# 04_DUT_Connector.net
KiCad netlist of a schematic drawn in Altium Designer
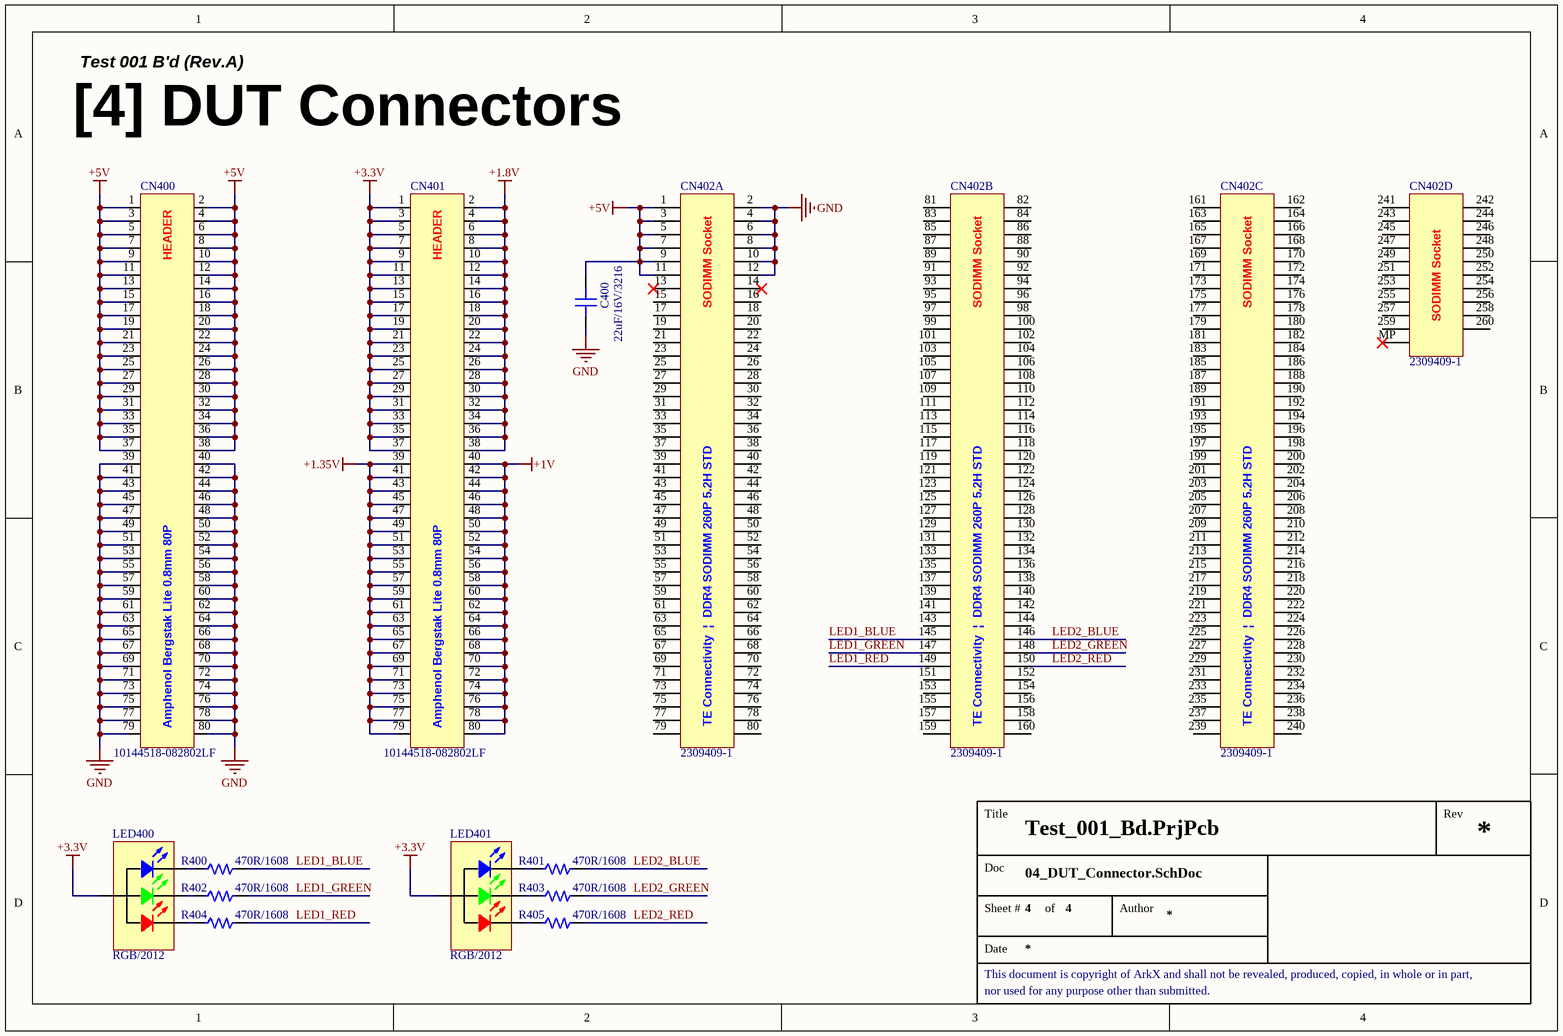
[diagram p0: 04_DUT_Connector.SchDoc]

(export (version "E")
  (design (tool "Eeschema 10.0.6"))
  (components
    (comp (ref "C400")
      (value "22uF/16V/3216")
      (footprint "CAP 3216 (1206_INCH) - H1.8MM")
      (description "Ceramic CAP_22uF/16V/3216")
      (fields (field (name "LCSC PART #") "C12891"))
      (libsource (lib "Arkx") (part "CAP_22uF/16V/3216"))
    )
    (comp (ref "CN400")
      (value "10144518-082802LF")
      (footprint "10144518-082802LF")
      (description "BergStak® Lite 0.80mm, Board-to-Board Connector, 80 Positions, Dual Row, Vertical Header")
      (fields (field (name "MANUFACTURER") "Amphenol"))
      (libsource (lib "Arkx") (part "CON_10144518-082802LF"))
    )
    (comp (ref "CN401")
      (value "10144518-082802LF")
      (footprint "10144518-082802LF")
      (description "BergStak® Lite 0.80mm, Board-to-Board Connector, 80 Positions, Dual Row, Vertical Header")
      (fields (field (name "MANUFACTURER") "Amphenol"))
      (libsource (lib "Arkx") (part "CON_10144518-082802LF"))
    )
    (comp (ref "CN402")
      (value "2309409-1")
      (footprint "CON_SODIMM_2309409-1")
      (fields (field (name "MANUFACTURER") "TE Connectivity") (field (name "LCSC PART #") "C5164025"))
      (libsource (lib "Arkx") (part "CON_SODIMM_2309409-1"))
    )
    (comp (ref "LED400")
      (value "RGB/2012")
      (footprint "LED MHT170RGBCT")
      (fields (field (name "LCSC PART #") "C2962094"))
      (libsource (lib "Arkx") (part "LED_RGB_MHT170RGBCT"))
    )
    (comp (ref "LED401")
      (value "RGB/2012")
      (footprint "LED MHT170RGBCT")
      (fields (field (name "LCSC PART #") "C2962094"))
      (libsource (lib "Arkx") (part "LED_RGB_MHT170RGBCT"))
    )
    (comp (ref "R400")
      (value "470R/1608")
      (footprint "RES 1608 (0603_inch)")
      (description "RES_470R/1608/0.1W")
      (fields (field (name "LCSC PART #") "C23179"))
      (libsource (lib "Arkx") (part "RES_470R/1608/0.1W"))
    )
    (comp (ref "R401")
      (value "470R/1608")
      (footprint "RES 1608 (0603_inch)")
      (description "RES_470R/1608/0.1W")
      (fields (field (name "LCSC PART #") "C23179"))
      (libsource (lib "Arkx") (part "RES_470R/1608/0.1W"))
    )
    (comp (ref "R402")
      (value "470R/1608")
      (footprint "RES 1608 (0603_inch)")
      (description "RES_470R/1608/0.1W")
      (fields (field (name "LCSC PART #") "C23179"))
      (libsource (lib "Arkx") (part "RES_470R/1608/0.1W"))
    )
    (comp (ref "R403")
      (value "470R/1608")
      (footprint "RES 1608 (0603_inch)")
      (description "RES_470R/1608/0.1W")
      (fields (field (name "LCSC PART #") "C23179"))
      (libsource (lib "Arkx") (part "RES_470R/1608/0.1W"))
    )
    (comp (ref "R404")
      (value "470R/1608")
      (footprint "RES 1608 (0603_inch)")
      (description "RES_470R/1608/0.1W")
      (fields (field (name "LCSC PART #") "C23179"))
      (libsource (lib "Arkx") (part "RES_470R/1608/0.1W"))
    )
    (comp (ref "R405")
      (value "470R/1608")
      (footprint "RES 1608 (0603_inch)")
      (description "RES_470R/1608/0.1W")
      (fields (field (name "LCSC PART #") "C23179"))
      (libsource (lib "Arkx") (part "RES_470R/1608/0.1W"))
    )
  )
  (nets
    (net (code "1") (name "+1.8V") (class "Default")
      (node (ref "CN401") (pin "10") (pintype "passive"))
      (node (ref "CN401") (pin "12") (pintype "passive"))
      (node (ref "CN401") (pin "14") (pintype "passive"))
      (node (ref "CN401") (pin "16") (pintype "passive"))
      (node (ref "CN401") (pin "18") (pintype "passive"))
      (node (ref "CN401") (pin "2") (pintype "passive"))
      (node (ref "CN401") (pin "20") (pintype "passive"))
      (node (ref "CN401") (pin "22") (pintype "passive"))
      (node (ref "CN401") (pin "24") (pintype "passive"))
      (node (ref "CN401") (pin "26") (pintype "passive"))
      (node (ref "CN401") (pin "28") (pintype "passive"))
      (node (ref "CN401") (pin "30") (pintype "passive"))
      (node (ref "CN401") (pin "32") (pintype "passive"))
      (node (ref "CN401") (pin "34") (pintype "passive"))
      (node (ref "CN401") (pin "36") (pintype "passive"))
      (node (ref "CN401") (pin "38") (pintype "passive"))
      (node (ref "CN401") (pin "4") (pintype "passive"))
      (node (ref "CN401") (pin "6") (pintype "passive"))
      (node (ref "CN401") (pin "8") (pintype "passive"))
    )
    (net (code "2") (name "+1.35V") (class "Default")
      (node (ref "CN401") (pin "39") (pintype "passive"))
      (node (ref "CN401") (pin "41") (pintype "passive"))
      (node (ref "CN401") (pin "43") (pintype "passive"))
      (node (ref "CN401") (pin "45") (pintype "passive"))
      (node (ref "CN401") (pin "47") (pintype "passive"))
      (node (ref "CN401") (pin "49") (pintype "passive"))
      (node (ref "CN401") (pin "51") (pintype "passive"))
      (node (ref "CN401") (pin "53") (pintype "passive"))
      (node (ref "CN401") (pin "55") (pintype "passive"))
      (node (ref "CN401") (pin "57") (pintype "passive"))
      (node (ref "CN401") (pin "59") (pintype "passive"))
      (node (ref "CN401") (pin "61") (pintype "passive"))
      (node (ref "CN401") (pin "63") (pintype "passive"))
      (node (ref "CN401") (pin "65") (pintype "passive"))
      (node (ref "CN401") (pin "67") (pintype "passive"))
      (node (ref "CN401") (pin "69") (pintype "passive"))
      (node (ref "CN401") (pin "71") (pintype "passive"))
      (node (ref "CN401") (pin "73") (pintype "passive"))
      (node (ref "CN401") (pin "75") (pintype "passive"))
      (node (ref "CN401") (pin "77") (pintype "passive"))
      (node (ref "CN401") (pin "79") (pintype "passive"))
    )
    (net (code "3") (name "+1V") (class "Default")
      (node (ref "CN401") (pin "40") (pintype "passive"))
      (node (ref "CN401") (pin "42") (pintype "passive"))
      (node (ref "CN401") (pin "44") (pintype "passive"))
      (node (ref "CN401") (pin "46") (pintype "passive"))
      (node (ref "CN401") (pin "48") (pintype "passive"))
      (node (ref "CN401") (pin "50") (pintype "passive"))
      (node (ref "CN401") (pin "52") (pintype "passive"))
      (node (ref "CN401") (pin "54") (pintype "passive"))
      (node (ref "CN401") (pin "56") (pintype "passive"))
      (node (ref "CN401") (pin "58") (pintype "passive"))
      (node (ref "CN401") (pin "60") (pintype "passive"))
      (node (ref "CN401") (pin "62") (pintype "passive"))
      (node (ref "CN401") (pin "64") (pintype "passive"))
      (node (ref "CN401") (pin "66") (pintype "passive"))
      (node (ref "CN401") (pin "68") (pintype "passive"))
      (node (ref "CN401") (pin "70") (pintype "passive"))
      (node (ref "CN401") (pin "72") (pintype "passive"))
      (node (ref "CN401") (pin "74") (pintype "passive"))
      (node (ref "CN401") (pin "76") (pintype "passive"))
      (node (ref "CN401") (pin "78") (pintype "passive"))
      (node (ref "CN401") (pin "80") (pintype "passive"))
    )
    (net (code "4") (name "+3.3V") (class "Default")
      (node (ref "CN401") (pin "1") (pintype "passive"))
      (node (ref "CN401") (pin "11") (pintype "passive"))
      (node (ref "CN401") (pin "13") (pintype "passive"))
      (node (ref "CN401") (pin "15") (pintype "passive"))
      (node (ref "CN401") (pin "17") (pintype "passive"))
      (node (ref "CN401") (pin "19") (pintype "passive"))
      (node (ref "CN401") (pin "21") (pintype "passive"))
      (node (ref "CN401") (pin "23") (pintype "passive"))
      (node (ref "CN401") (pin "25") (pintype "passive"))
      (node (ref "CN401") (pin "27") (pintype "passive"))
      (node (ref "CN401") (pin "29") (pintype "passive"))
      (node (ref "CN401") (pin "3") (pintype "passive"))
      (node (ref "CN401") (pin "31") (pintype "passive"))
      (node (ref "CN401") (pin "33") (pintype "passive"))
      (node (ref "CN401") (pin "35") (pintype "passive"))
      (node (ref "CN401") (pin "37") (pintype "passive"))
      (node (ref "CN401") (pin "5") (pintype "passive"))
      (node (ref "CN401") (pin "7") (pintype "passive"))
      (node (ref "CN401") (pin "9") (pintype "passive"))
      (node (ref "LED400") (pin "4") (pinfunction "Common_Anode_4") (pintype "passive"))
      (node (ref "LED401") (pin "4") (pinfunction "Common_Anode_4") (pintype "passive"))
    )
    (net (code "5") (name "+5V") (class "Default")
      (node (ref "C400") (pin "2") (pinfunction "2_2") (pintype "passive"))
      (node (ref "CN400") (pin "1") (pintype "passive"))
      (node (ref "CN400") (pin "10") (pintype "passive"))
      (node (ref "CN400") (pin "11") (pintype "passive"))
      (node (ref "CN400") (pin "12") (pintype "passive"))
      (node (ref "CN400") (pin "13") (pintype "passive"))
      (node (ref "CN400") (pin "14") (pintype "passive"))
      (node (ref "CN400") (pin "15") (pintype "passive"))
      (node (ref "CN400") (pin "16") (pintype "passive"))
      (node (ref "CN400") (pin "17") (pintype "passive"))
      (node (ref "CN400") (pin "18") (pintype "passive"))
      (node (ref "CN400") (pin "19") (pintype "passive"))
      (node (ref "CN400") (pin "2") (pintype "passive"))
      (node (ref "CN400") (pin "20") (pintype "passive"))
      (node (ref "CN400") (pin "21") (pintype "passive"))
      (node (ref "CN400") (pin "22") (pintype "passive"))
      (node (ref "CN400") (pin "23") (pintype "passive"))
      (node (ref "CN400") (pin "24") (pintype "passive"))
      (node (ref "CN400") (pin "25") (pintype "passive"))
      (node (ref "CN400") (pin "26") (pintype "passive"))
      (node (ref "CN400") (pin "27") (pintype "passive"))
      (node (ref "CN400") (pin "28") (pintype "passive"))
      (node (ref "CN400") (pin "29") (pintype "passive"))
      (node (ref "CN400") (pin "3") (pintype "passive"))
      (node (ref "CN400") (pin "30") (pintype "passive"))
      (node (ref "CN400") (pin "31") (pintype "passive"))
      (node (ref "CN400") (pin "32") (pintype "passive"))
      (node (ref "CN400") (pin "33") (pintype "passive"))
      (node (ref "CN400") (pin "34") (pintype "passive"))
      (node (ref "CN400") (pin "35") (pintype "passive"))
      (node (ref "CN400") (pin "36") (pintype "passive"))
      (node (ref "CN400") (pin "37") (pintype "passive"))
      (node (ref "CN400") (pin "38") (pintype "passive"))
      (node (ref "CN400") (pin "4") (pintype "passive"))
      (node (ref "CN400") (pin "5") (pintype "passive"))
      (node (ref "CN400") (pin "6") (pintype "passive"))
      (node (ref "CN400") (pin "7") (pintype "passive"))
      (node (ref "CN400") (pin "8") (pintype "passive"))
      (node (ref "CN400") (pin "9") (pintype "passive"))
      (node (ref "CN402") (pin "1") (pinfunction "1_1") (pintype "passive"))
      (node (ref "CN402") (pin "11") (pinfunction "11_11") (pintype "passive"))
      (node (ref "CN402") (pin "3") (pinfunction "3_3") (pintype "passive"))
      (node (ref "CN402") (pin "5") (pinfunction "5_5") (pintype "passive"))
      (node (ref "CN402") (pin "7") (pinfunction "7_7") (pintype "passive"))
      (node (ref "CN402") (pin "9") (pinfunction "9_9") (pintype "passive"))
    )
    (net (code "6") (name "/LED1_BLUE") (class "Default")
      (node (ref "CN402") (pin "145") (pinfunction "145_145") (pintype "passive"))
      (node (ref "R400") (pin "2") (pinfunction "2_2") (pintype "passive"))
    )
    (net (code "7") (name "/LED1_GREEN") (class "Default")
      (node (ref "CN402") (pin "147") (pinfunction "147_147") (pintype "passive"))
      (node (ref "R402") (pin "2") (pinfunction "2_2") (pintype "passive"))
    )
    (net (code "8") (name "/LED1_RED") (class "Default")
      (node (ref "CN402") (pin "149") (pinfunction "149_149") (pintype "passive"))
      (node (ref "R404") (pin "2") (pinfunction "2_2") (pintype "passive"))
    )
    (net (code "9") (name "/LED2_BLUE") (class "Default")
      (node (ref "CN402") (pin "146") (pinfunction "146_146") (pintype "passive"))
      (node (ref "R401") (pin "2") (pinfunction "2_2") (pintype "passive"))
    )
    (net (code "10") (name "/LED2_GREEN") (class "Default")
      (node (ref "CN402") (pin "148") (pinfunction "148_148") (pintype "passive"))
      (node (ref "R403") (pin "2") (pinfunction "2_2") (pintype "passive"))
    )
    (net (code "11") (name "/LED2_RED") (class "Default")
      (node (ref "CN402") (pin "150") (pinfunction "150_150") (pintype "passive"))
      (node (ref "R405") (pin "2") (pinfunction "2_2") (pintype "passive"))
    )
    (net (code "12") (name "GND") (class "Default")
      (node (ref "C400") (pin "1") (pinfunction "1_1") (pintype "passive"))
      (node (ref "CN400") (pin "39") (pintype "passive"))
      (node (ref "CN400") (pin "40") (pintype "passive"))
      (node (ref "CN400") (pin "41") (pintype "passive"))
      (node (ref "CN400") (pin "42") (pintype "passive"))
      (node (ref "CN400") (pin "43") (pintype "passive"))
      (node (ref "CN400") (pin "44") (pintype "passive"))
      (node (ref "CN400") (pin "45") (pintype "passive"))
      (node (ref "CN400") (pin "46") (pintype "passive"))
      (node (ref "CN400") (pin "47") (pintype "passive"))
      (node (ref "CN400") (pin "48") (pintype "passive"))
      (node (ref "CN400") (pin "49") (pintype "passive"))
      (node (ref "CN400") (pin "50") (pintype "passive"))
      (node (ref "CN400") (pin "51") (pintype "passive"))
      (node (ref "CN400") (pin "52") (pintype "passive"))
      (node (ref "CN400") (pin "53") (pintype "passive"))
      (node (ref "CN400") (pin "54") (pintype "passive"))
      (node (ref "CN400") (pin "55") (pintype "passive"))
      (node (ref "CN400") (pin "56") (pintype "passive"))
      (node (ref "CN400") (pin "57") (pintype "passive"))
      (node (ref "CN400") (pin "58") (pintype "passive"))
      (node (ref "CN400") (pin "59") (pintype "passive"))
      (node (ref "CN400") (pin "60") (pintype "passive"))
      (node (ref "CN400") (pin "61") (pintype "passive"))
      (node (ref "CN400") (pin "62") (pintype "passive"))
      (node (ref "CN400") (pin "63") (pintype "passive"))
      (node (ref "CN400") (pin "64") (pintype "passive"))
      (node (ref "CN400") (pin "65") (pintype "passive"))
      (node (ref "CN400") (pin "66") (pintype "passive"))
      (node (ref "CN400") (pin "67") (pintype "passive"))
      (node (ref "CN400") (pin "68") (pintype "passive"))
      (node (ref "CN400") (pin "69") (pintype "passive"))
      (node (ref "CN400") (pin "70") (pintype "passive"))
      (node (ref "CN400") (pin "71") (pintype "passive"))
      (node (ref "CN400") (pin "72") (pintype "passive"))
      (node (ref "CN400") (pin "73") (pintype "passive"))
      (node (ref "CN400") (pin "74") (pintype "passive"))
      (node (ref "CN400") (pin "75") (pintype "passive"))
      (node (ref "CN400") (pin "76") (pintype "passive"))
      (node (ref "CN400") (pin "77") (pintype "passive"))
      (node (ref "CN400") (pin "78") (pintype "passive"))
      (node (ref "CN400") (pin "79") (pintype "passive"))
      (node (ref "CN400") (pin "80") (pintype "passive"))
      (node (ref "CN402") (pin "10") (pinfunction "10_10") (pintype "passive"))
      (node (ref "CN402") (pin "12") (pinfunction "12_12") (pintype "passive"))
      (node (ref "CN402") (pin "2") (pinfunction "2_2") (pintype "passive"))
      (node (ref "CN402") (pin "4") (pinfunction "4_4") (pintype "passive"))
      (node (ref "CN402") (pin "6") (pinfunction "6_6") (pintype "passive"))
      (node (ref "CN402") (pin "8") (pinfunction "8_8") (pintype "passive"))
    )
    (net (code "13") (name "Net-(LED400-BLUE)") (class "Default")
      (node (ref "LED400") (pin "3") (pinfunction "BLUE_3") (pintype "passive"))
      (node (ref "R400") (pin "1") (pinfunction "1_1") (pintype "passive"))
    )
    (net (code "14") (name "Net-(LED400-GREEN)") (class "Default")
      (node (ref "LED400") (pin "2") (pinfunction "GREEN_2") (pintype "passive"))
      (node (ref "R402") (pin "1") (pinfunction "1_1") (pintype "passive"))
    )
    (net (code "15") (name "Net-(LED400-RED)") (class "Default")
      (node (ref "LED400") (pin "1") (pinfunction "RED_1") (pintype "passive"))
      (node (ref "R404") (pin "1") (pinfunction "1_1") (pintype "passive"))
    )
    (net (code "16") (name "Net-(LED401-BLUE)") (class "Default")
      (node (ref "LED401") (pin "3") (pinfunction "BLUE_3") (pintype "passive"))
      (node (ref "R401") (pin "1") (pinfunction "1_1") (pintype "passive"))
    )
    (net (code "17") (name "Net-(LED401-GREEN)") (class "Default")
      (node (ref "LED401") (pin "2") (pinfunction "GREEN_2") (pintype "passive"))
      (node (ref "R403") (pin "1") (pinfunction "1_1") (pintype "passive"))
    )
    (net (code "18") (name "Net-(LED401-RED)") (class "Default")
      (node (ref "LED401") (pin "1") (pinfunction "RED_1") (pintype "passive"))
      (node (ref "R405") (pin "1") (pinfunction "1_1") (pintype "passive"))
    )
    (net (code "19") (name "unconnected-(CN402-Pad13)") (class "Default")
      (node (ref "CN402") (pin "13") (pinfunction "13_13") (pintype "passive+no_connect"))
    )
    (net (code "20") (name "unconnected-(CN402-Pad14)") (class "Default")
      (node (ref "CN402") (pin "14") (pinfunction "14_14") (pintype "passive+no_connect"))
    )
    (net (code "21") (name "unconnected-(CN402-Pad15)") (class "Default")
      (node (ref "CN402") (pin "15") (pinfunction "15_15") (pintype "passive"))
    )
    (net (code "22") (name "unconnected-(CN402-Pad16)") (class "Default")
      (node (ref "CN402") (pin "16") (pinfunction "16_16") (pintype "passive"))
    )
    (net (code "23") (name "unconnected-(CN402-Pad17)") (class "Default")
      (node (ref "CN402") (pin "17") (pinfunction "17_17") (pintype "passive"))
    )
    (net (code "24") (name "unconnected-(CN402-Pad18)") (class "Default")
      (node (ref "CN402") (pin "18") (pinfunction "18_18") (pintype "passive"))
    )
    (net (code "25") (name "unconnected-(CN402-Pad19)") (class "Default")
      (node (ref "CN402") (pin "19") (pinfunction "19_19") (pintype "passive"))
    )
    (net (code "26") (name "unconnected-(CN402-Pad20)") (class "Default")
      (node (ref "CN402") (pin "20") (pinfunction "20_20") (pintype "passive"))
    )
    (net (code "27") (name "unconnected-(CN402-Pad21)") (class "Default")
      (node (ref "CN402") (pin "21") (pinfunction "21_21") (pintype "passive"))
    )
    (net (code "28") (name "unconnected-(CN402-Pad22)") (class "Default")
      (node (ref "CN402") (pin "22") (pinfunction "22_22") (pintype "passive"))
    )
    (net (code "29") (name "unconnected-(CN402-Pad23)") (class "Default")
      (node (ref "CN402") (pin "23") (pinfunction "23_23") (pintype "passive"))
    )
    (net (code "30") (name "unconnected-(CN402-Pad24)") (class "Default")
      (node (ref "CN402") (pin "24") (pinfunction "24_24") (pintype "passive"))
    )
    (net (code "31") (name "unconnected-(CN402-Pad25)") (class "Default")
      (node (ref "CN402") (pin "25") (pinfunction "25_25") (pintype "passive"))
    )
    (net (code "32") (name "unconnected-(CN402-Pad26)") (class "Default")
      (node (ref "CN402") (pin "26") (pinfunction "26_26") (pintype "passive"))
    )
    (net (code "33") (name "unconnected-(CN402-Pad27)") (class "Default")
      (node (ref "CN402") (pin "27") (pinfunction "27_27") (pintype "passive"))
    )
    (net (code "34") (name "unconnected-(CN402-Pad28)") (class "Default")
      (node (ref "CN402") (pin "28") (pinfunction "28_28") (pintype "passive"))
    )
    (net (code "35") (name "unconnected-(CN402-Pad29)") (class "Default")
      (node (ref "CN402") (pin "29") (pinfunction "29_29") (pintype "passive"))
    )
    (net (code "36") (name "unconnected-(CN402-Pad30)") (class "Default")
      (node (ref "CN402") (pin "30") (pinfunction "30_30") (pintype "passive"))
    )
    (net (code "37") (name "unconnected-(CN402-Pad31)") (class "Default")
      (node (ref "CN402") (pin "31") (pinfunction "31_31") (pintype "passive"))
    )
    (net (code "38") (name "unconnected-(CN402-Pad32)") (class "Default")
      (node (ref "CN402") (pin "32") (pinfunction "32_32") (pintype "passive"))
    )
    (net (code "39") (name "unconnected-(CN402-Pad33)") (class "Default")
      (node (ref "CN402") (pin "33") (pinfunction "33_33") (pintype "passive"))
    )
    (net (code "40") (name "unconnected-(CN402-Pad34)") (class "Default")
      (node (ref "CN402") (pin "34") (pinfunction "34_34") (pintype "passive"))
    )
    (net (code "41") (name "unconnected-(CN402-Pad35)") (class "Default")
      (node (ref "CN402") (pin "35") (pinfunction "35_35") (pintype "passive"))
    )
    (net (code "42") (name "unconnected-(CN402-Pad36)") (class "Default")
      (node (ref "CN402") (pin "36") (pinfunction "36_36") (pintype "passive"))
    )
    (net (code "43") (name "unconnected-(CN402-Pad37)") (class "Default")
      (node (ref "CN402") (pin "37") (pinfunction "37_37") (pintype "passive"))
    )
    (net (code "44") (name "unconnected-(CN402-Pad38)") (class "Default")
      (node (ref "CN402") (pin "38") (pinfunction "38_38") (pintype "passive"))
    )
    (net (code "45") (name "unconnected-(CN402-Pad39)") (class "Default")
      (node (ref "CN402") (pin "39") (pinfunction "39_39") (pintype "passive"))
    )
    (net (code "46") (name "unconnected-(CN402-Pad40)") (class "Default")
      (node (ref "CN402") (pin "40") (pinfunction "40_40") (pintype "passive"))
    )
    (net (code "47") (name "unconnected-(CN402-Pad41)") (class "Default")
      (node (ref "CN402") (pin "41") (pinfunction "41_41") (pintype "passive"))
    )
    (net (code "48") (name "unconnected-(CN402-Pad42)") (class "Default")
      (node (ref "CN402") (pin "42") (pinfunction "42_42") (pintype "passive"))
    )
    (net (code "49") (name "unconnected-(CN402-Pad43)") (class "Default")
      (node (ref "CN402") (pin "43") (pinfunction "43_43") (pintype "passive"))
    )
    (net (code "50") (name "unconnected-(CN402-Pad44)") (class "Default")
      (node (ref "CN402") (pin "44") (pinfunction "44_44") (pintype "passive"))
    )
    (net (code "51") (name "unconnected-(CN402-Pad45)") (class "Default")
      (node (ref "CN402") (pin "45") (pinfunction "45_45") (pintype "passive"))
    )
    (net (code "52") (name "unconnected-(CN402-Pad46)") (class "Default")
      (node (ref "CN402") (pin "46") (pinfunction "46_46") (pintype "passive"))
    )
    (net (code "53") (name "unconnected-(CN402-Pad47)") (class "Default")
      (node (ref "CN402") (pin "47") (pinfunction "47_47") (pintype "passive"))
    )
    (net (code "54") (name "unconnected-(CN402-Pad48)") (class "Default")
      (node (ref "CN402") (pin "48") (pinfunction "48_48") (pintype "passive"))
    )
    (net (code "55") (name "unconnected-(CN402-Pad49)") (class "Default")
      (node (ref "CN402") (pin "49") (pinfunction "49_49") (pintype "passive"))
    )
    (net (code "56") (name "unconnected-(CN402-Pad50)") (class "Default")
      (node (ref "CN402") (pin "50") (pinfunction "50_50") (pintype "passive"))
    )
    (net (code "57") (name "unconnected-(CN402-Pad51)") (class "Default")
      (node (ref "CN402") (pin "51") (pinfunction "51_51") (pintype "passive"))
    )
    (net (code "58") (name "unconnected-(CN402-Pad52)") (class "Default")
      (node (ref "CN402") (pin "52") (pinfunction "52_52") (pintype "passive"))
    )
    (net (code "59") (name "unconnected-(CN402-Pad53)") (class "Default")
      (node (ref "CN402") (pin "53") (pinfunction "53_53") (pintype "passive"))
    )
    (net (code "60") (name "unconnected-(CN402-Pad54)") (class "Default")
      (node (ref "CN402") (pin "54") (pinfunction "54_54") (pintype "passive"))
    )
    (net (code "61") (name "unconnected-(CN402-Pad55)") (class "Default")
      (node (ref "CN402") (pin "55") (pinfunction "55_55") (pintype "passive"))
    )
    (net (code "62") (name "unconnected-(CN402-Pad56)") (class "Default")
      (node (ref "CN402") (pin "56") (pinfunction "56_56") (pintype "passive"))
    )
    (net (code "63") (name "unconnected-(CN402-Pad57)") (class "Default")
      (node (ref "CN402") (pin "57") (pinfunction "57_57") (pintype "passive"))
    )
    (net (code "64") (name "unconnected-(CN402-Pad58)") (class "Default")
      (node (ref "CN402") (pin "58") (pinfunction "58_58") (pintype "passive"))
    )
    (net (code "65") (name "unconnected-(CN402-Pad59)") (class "Default")
      (node (ref "CN402") (pin "59") (pinfunction "59_59") (pintype "passive"))
    )
    (net (code "66") (name "unconnected-(CN402-Pad60)") (class "Default")
      (node (ref "CN402") (pin "60") (pinfunction "60_60") (pintype "passive"))
    )
    (net (code "67") (name "unconnected-(CN402-Pad61)") (class "Default")
      (node (ref "CN402") (pin "61") (pinfunction "61_61") (pintype "passive"))
    )
    (net (code "68") (name "unconnected-(CN402-Pad62)") (class "Default")
      (node (ref "CN402") (pin "62") (pinfunction "62_62") (pintype "passive"))
    )
    (net (code "69") (name "unconnected-(CN402-Pad63)") (class "Default")
      (node (ref "CN402") (pin "63") (pinfunction "63_63") (pintype "passive"))
    )
    (net (code "70") (name "unconnected-(CN402-Pad64)") (class "Default")
      (node (ref "CN402") (pin "64") (pinfunction "64_64") (pintype "passive"))
    )
    (net (code "71") (name "unconnected-(CN402-Pad65)") (class "Default")
      (node (ref "CN402") (pin "65") (pinfunction "65_65") (pintype "passive"))
    )
    (net (code "72") (name "unconnected-(CN402-Pad66)") (class "Default")
      (node (ref "CN402") (pin "66") (pinfunction "66_66") (pintype "passive"))
    )
    (net (code "73") (name "unconnected-(CN402-Pad67)") (class "Default")
      (node (ref "CN402") (pin "67") (pinfunction "67_67") (pintype "passive"))
    )
    (net (code "74") (name "unconnected-(CN402-Pad68)") (class "Default")
      (node (ref "CN402") (pin "68") (pinfunction "68_68") (pintype "passive"))
    )
    (net (code "75") (name "unconnected-(CN402-Pad69)") (class "Default")
      (node (ref "CN402") (pin "69") (pinfunction "69_69") (pintype "passive"))
    )
    (net (code "76") (name "unconnected-(CN402-Pad70)") (class "Default")
      (node (ref "CN402") (pin "70") (pinfunction "70_70") (pintype "passive"))
    )
    (net (code "77") (name "unconnected-(CN402-Pad71)") (class "Default")
      (node (ref "CN402") (pin "71") (pinfunction "71_71") (pintype "passive"))
    )
    (net (code "78") (name "unconnected-(CN402-Pad72)") (class "Default")
      (node (ref "CN402") (pin "72") (pinfunction "72_72") (pintype "passive"))
    )
    (net (code "79") (name "unconnected-(CN402-Pad73)") (class "Default")
      (node (ref "CN402") (pin "73") (pinfunction "73_73") (pintype "passive"))
    )
    (net (code "80") (name "unconnected-(CN402-Pad74)") (class "Default")
      (node (ref "CN402") (pin "74") (pinfunction "74_74") (pintype "passive"))
    )
    (net (code "81") (name "unconnected-(CN402-Pad75)") (class "Default")
      (node (ref "CN402") (pin "75") (pinfunction "75_75") (pintype "passive"))
    )
    (net (code "82") (name "unconnected-(CN402-Pad76)") (class "Default")
      (node (ref "CN402") (pin "76") (pinfunction "76_76") (pintype "passive"))
    )
    (net (code "83") (name "unconnected-(CN402-Pad77)") (class "Default")
      (node (ref "CN402") (pin "77") (pinfunction "77_77") (pintype "passive"))
    )
    (net (code "84") (name "unconnected-(CN402-Pad78)") (class "Default")
      (node (ref "CN402") (pin "78") (pinfunction "78_78") (pintype "passive"))
    )
    (net (code "85") (name "unconnected-(CN402-Pad79)") (class "Default")
      (node (ref "CN402") (pin "79") (pinfunction "79_79") (pintype "passive"))
    )
    (net (code "86") (name "unconnected-(CN402-Pad80)") (class "Default")
      (node (ref "CN402") (pin "80") (pinfunction "80_80") (pintype "passive"))
    )
    (net (code "87") (name "unconnected-(CN402-Pad81)") (class "Default")
      (node (ref "CN402") (pin "81") (pinfunction "81_81") (pintype "passive"))
    )
    (net (code "88") (name "unconnected-(CN402-Pad82)") (class "Default")
      (node (ref "CN402") (pin "82") (pinfunction "82_82") (pintype "passive"))
    )
    (net (code "89") (name "unconnected-(CN402-Pad83)") (class "Default")
      (node (ref "CN402") (pin "83") (pinfunction "83_83") (pintype "passive"))
    )
    (net (code "90") (name "unconnected-(CN402-Pad84)") (class "Default")
      (node (ref "CN402") (pin "84") (pinfunction "84_84") (pintype "passive"))
    )
    (net (code "91") (name "unconnected-(CN402-Pad85)") (class "Default")
      (node (ref "CN402") (pin "85") (pinfunction "85_85") (pintype "passive"))
    )
    (net (code "92") (name "unconnected-(CN402-Pad86)") (class "Default")
      (node (ref "CN402") (pin "86") (pinfunction "86_86") (pintype "passive"))
    )
    (net (code "93") (name "unconnected-(CN402-Pad87)") (class "Default")
      (node (ref "CN402") (pin "87") (pinfunction "87_87") (pintype "passive"))
    )
    (net (code "94") (name "unconnected-(CN402-Pad88)") (class "Default")
      (node (ref "CN402") (pin "88") (pinfunction "88_88") (pintype "passive"))
    )
    (net (code "95") (name "unconnected-(CN402-Pad89)") (class "Default")
      (node (ref "CN402") (pin "89") (pinfunction "89_89") (pintype "passive"))
    )
    (net (code "96") (name "unconnected-(CN402-Pad90)") (class "Default")
      (node (ref "CN402") (pin "90") (pinfunction "90_90") (pintype "passive"))
    )
    (net (code "97") (name "unconnected-(CN402-Pad91)") (class "Default")
      (node (ref "CN402") (pin "91") (pinfunction "91_91") (pintype "passive"))
    )
    (net (code "98") (name "unconnected-(CN402-Pad92)") (class "Default")
      (node (ref "CN402") (pin "92") (pinfunction "92_92") (pintype "passive"))
    )
    (net (code "99") (name "unconnected-(CN402-Pad93)") (class "Default")
      (node (ref "CN402") (pin "93") (pinfunction "93_93") (pintype "passive"))
    )
    (net (code "100") (name "unconnected-(CN402-Pad94)") (class "Default")
      (node (ref "CN402") (pin "94") (pinfunction "94_94") (pintype "passive"))
    )
    (net (code "101") (name "unconnected-(CN402-Pad95)") (class "Default")
      (node (ref "CN402") (pin "95") (pinfunction "95_95") (pintype "passive"))
    )
    (net (code "102") (name "unconnected-(CN402-Pad96)") (class "Default")
      (node (ref "CN402") (pin "96") (pinfunction "96_96") (pintype "passive"))
    )
    (net (code "103") (name "unconnected-(CN402-Pad97)") (class "Default")
      (node (ref "CN402") (pin "97") (pinfunction "97_97") (pintype "passive"))
    )
    (net (code "104") (name "unconnected-(CN402-Pad98)") (class "Default")
      (node (ref "CN402") (pin "98") (pinfunction "98_98") (pintype "passive"))
    )
    (net (code "105") (name "unconnected-(CN402-Pad99)") (class "Default")
      (node (ref "CN402") (pin "99") (pinfunction "99_99") (pintype "passive"))
    )
    (net (code "106") (name "unconnected-(CN402-Pad100)") (class "Default")
      (node (ref "CN402") (pin "100") (pinfunction "100_100") (pintype "passive"))
    )
    (net (code "107") (name "unconnected-(CN402-Pad101)") (class "Default")
      (node (ref "CN402") (pin "101") (pinfunction "101_101") (pintype "passive"))
    )
    (net (code "108") (name "unconnected-(CN402-Pad102)") (class "Default")
      (node (ref "CN402") (pin "102") (pinfunction "102_102") (pintype "passive"))
    )
    (net (code "109") (name "unconnected-(CN402-Pad103)") (class "Default")
      (node (ref "CN402") (pin "103") (pinfunction "103_103") (pintype "passive"))
    )
    (net (code "110") (name "unconnected-(CN402-Pad104)") (class "Default")
      (node (ref "CN402") (pin "104") (pinfunction "104_104") (pintype "passive"))
    )
    (net (code "111") (name "unconnected-(CN402-Pad105)") (class "Default")
      (node (ref "CN402") (pin "105") (pinfunction "105_105") (pintype "passive"))
    )
    (net (code "112") (name "unconnected-(CN402-Pad106)") (class "Default")
      (node (ref "CN402") (pin "106") (pinfunction "106_106") (pintype "passive"))
    )
    (net (code "113") (name "unconnected-(CN402-Pad107)") (class "Default")
      (node (ref "CN402") (pin "107") (pinfunction "107_107") (pintype "passive"))
    )
    (net (code "114") (name "unconnected-(CN402-Pad108)") (class "Default")
      (node (ref "CN402") (pin "108") (pinfunction "108_108") (pintype "passive"))
    )
    (net (code "115") (name "unconnected-(CN402-Pad109)") (class "Default")
      (node (ref "CN402") (pin "109") (pinfunction "109_109") (pintype "passive"))
    )
    (net (code "116") (name "unconnected-(CN402-Pad110)") (class "Default")
      (node (ref "CN402") (pin "110") (pinfunction "110_110") (pintype "passive"))
    )
    (net (code "117") (name "unconnected-(CN402-Pad111)") (class "Default")
      (node (ref "CN402") (pin "111") (pinfunction "111_111") (pintype "passive"))
    )
    (net (code "118") (name "unconnected-(CN402-Pad112)") (class "Default")
      (node (ref "CN402") (pin "112") (pinfunction "112_112") (pintype "passive"))
    )
    (net (code "119") (name "unconnected-(CN402-Pad113)") (class "Default")
      (node (ref "CN402") (pin "113") (pinfunction "113_113") (pintype "passive"))
    )
    (net (code "120") (name "unconnected-(CN402-Pad114)") (class "Default")
      (node (ref "CN402") (pin "114") (pinfunction "114_114") (pintype "passive"))
    )
    (net (code "121") (name "unconnected-(CN402-Pad115)") (class "Default")
      (node (ref "CN402") (pin "115") (pinfunction "115_115") (pintype "passive"))
    )
    (net (code "122") (name "unconnected-(CN402-Pad116)") (class "Default")
      (node (ref "CN402") (pin "116") (pinfunction "116_116") (pintype "passive"))
    )
    (net (code "123") (name "unconnected-(CN402-Pad117)") (class "Default")
      (node (ref "CN402") (pin "117") (pinfunction "117_117") (pintype "passive"))
    )
    (net (code "124") (name "unconnected-(CN402-Pad118)") (class "Default")
      (node (ref "CN402") (pin "118") (pinfunction "118_118") (pintype "passive"))
    )
    (net (code "125") (name "unconnected-(CN402-Pad119)") (class "Default")
      (node (ref "CN402") (pin "119") (pinfunction "119_119") (pintype "passive"))
    )
    (net (code "126") (name "unconnected-(CN402-Pad120)") (class "Default")
      (node (ref "CN402") (pin "120") (pinfunction "120_120") (pintype "passive"))
    )
    (net (code "127") (name "unconnected-(CN402-Pad121)") (class "Default")
      (node (ref "CN402") (pin "121") (pinfunction "121_121") (pintype "passive"))
    )
    (net (code "128") (name "unconnected-(CN402-Pad122)") (class "Default")
      (node (ref "CN402") (pin "122") (pinfunction "122_122") (pintype "passive"))
    )
    (net (code "129") (name "unconnected-(CN402-Pad123)") (class "Default")
      (node (ref "CN402") (pin "123") (pinfunction "123_123") (pintype "passive"))
    )
    (net (code "130") (name "unconnected-(CN402-Pad124)") (class "Default")
      (node (ref "CN402") (pin "124") (pinfunction "124_124") (pintype "passive"))
    )
    (net (code "131") (name "unconnected-(CN402-Pad125)") (class "Default")
      (node (ref "CN402") (pin "125") (pinfunction "125_125") (pintype "passive"))
    )
    (net (code "132") (name "unconnected-(CN402-Pad126)") (class "Default")
      (node (ref "CN402") (pin "126") (pinfunction "126_126") (pintype "passive"))
    )
    (net (code "133") (name "unconnected-(CN402-Pad127)") (class "Default")
      (node (ref "CN402") (pin "127") (pinfunction "127_127") (pintype "passive"))
    )
    (net (code "134") (name "unconnected-(CN402-Pad128)") (class "Default")
      (node (ref "CN402") (pin "128") (pinfunction "128_128") (pintype "passive"))
    )
    (net (code "135") (name "unconnected-(CN402-Pad129)") (class "Default")
      (node (ref "CN402") (pin "129") (pinfunction "129_129") (pintype "passive"))
    )
    (net (code "136") (name "unconnected-(CN402-Pad130)") (class "Default")
      (node (ref "CN402") (pin "130") (pinfunction "130_130") (pintype "passive"))
    )
    (net (code "137") (name "unconnected-(CN402-Pad131)") (class "Default")
      (node (ref "CN402") (pin "131") (pinfunction "131_131") (pintype "passive"))
    )
    (net (code "138") (name "unconnected-(CN402-Pad132)") (class "Default")
      (node (ref "CN402") (pin "132") (pinfunction "132_132") (pintype "passive"))
    )
    (net (code "139") (name "unconnected-(CN402-Pad133)") (class "Default")
      (node (ref "CN402") (pin "133") (pinfunction "133_133") (pintype "passive"))
    )
    (net (code "140") (name "unconnected-(CN402-Pad134)") (class "Default")
      (node (ref "CN402") (pin "134") (pinfunction "134_134") (pintype "passive"))
    )
    (net (code "141") (name "unconnected-(CN402-Pad135)") (class "Default")
      (node (ref "CN402") (pin "135") (pinfunction "135_135") (pintype "passive"))
    )
    (net (code "142") (name "unconnected-(CN402-Pad136)") (class "Default")
      (node (ref "CN402") (pin "136") (pinfunction "136_136") (pintype "passive"))
    )
    (net (code "143") (name "unconnected-(CN402-Pad137)") (class "Default")
      (node (ref "CN402") (pin "137") (pinfunction "137_137") (pintype "passive"))
    )
    (net (code "144") (name "unconnected-(CN402-Pad138)") (class "Default")
      (node (ref "CN402") (pin "138") (pinfunction "138_138") (pintype "passive"))
    )
    (net (code "145") (name "unconnected-(CN402-Pad139)") (class "Default")
      (node (ref "CN402") (pin "139") (pinfunction "139_139") (pintype "passive"))
    )
    (net (code "146") (name "unconnected-(CN402-Pad140)") (class "Default")
      (node (ref "CN402") (pin "140") (pinfunction "140_140") (pintype "passive"))
    )
    (net (code "147") (name "unconnected-(CN402-Pad141)") (class "Default")
      (node (ref "CN402") (pin "141") (pinfunction "141_141") (pintype "passive"))
    )
    (net (code "148") (name "unconnected-(CN402-Pad142)") (class "Default")
      (node (ref "CN402") (pin "142") (pinfunction "142_142") (pintype "passive"))
    )
    (net (code "149") (name "unconnected-(CN402-Pad143)") (class "Default")
      (node (ref "CN402") (pin "143") (pinfunction "143_143") (pintype "passive"))
    )
    (net (code "150") (name "unconnected-(CN402-Pad144)") (class "Default")
      (node (ref "CN402") (pin "144") (pinfunction "144_144") (pintype "passive"))
    )
    (net (code "151") (name "unconnected-(CN402-Pad151)") (class "Default")
      (node (ref "CN402") (pin "151") (pinfunction "151_151") (pintype "passive"))
    )
    (net (code "152") (name "unconnected-(CN402-Pad152)") (class "Default")
      (node (ref "CN402") (pin "152") (pinfunction "152_152") (pintype "passive"))
    )
    (net (code "153") (name "unconnected-(CN402-Pad153)") (class "Default")
      (node (ref "CN402") (pin "153") (pinfunction "153_153") (pintype "passive"))
    )
    (net (code "154") (name "unconnected-(CN402-Pad154)") (class "Default")
      (node (ref "CN402") (pin "154") (pinfunction "154_154") (pintype "passive"))
    )
    (net (code "155") (name "unconnected-(CN402-Pad155)") (class "Default")
      (node (ref "CN402") (pin "155") (pinfunction "155_155") (pintype "passive"))
    )
    (net (code "156") (name "unconnected-(CN402-Pad156)") (class "Default")
      (node (ref "CN402") (pin "156") (pinfunction "156_156") (pintype "passive"))
    )
    (net (code "157") (name "unconnected-(CN402-Pad157)") (class "Default")
      (node (ref "CN402") (pin "157") (pinfunction "157_157") (pintype "passive"))
    )
    (net (code "158") (name "unconnected-(CN402-Pad158)") (class "Default")
      (node (ref "CN402") (pin "158") (pinfunction "158_158") (pintype "passive"))
    )
    (net (code "159") (name "unconnected-(CN402-Pad159)") (class "Default")
      (node (ref "CN402") (pin "159") (pinfunction "159_159") (pintype "passive"))
    )
    (net (code "160") (name "unconnected-(CN402-Pad160)") (class "Default")
      (node (ref "CN402") (pin "160") (pinfunction "160_160") (pintype "passive"))
    )
    (net (code "161") (name "unconnected-(CN402-Pad161)") (class "Default")
      (node (ref "CN402") (pin "161") (pinfunction "161_161") (pintype "passive"))
    )
    (net (code "162") (name "unconnected-(CN402-Pad162)") (class "Default")
      (node (ref "CN402") (pin "162") (pinfunction "162_162") (pintype "passive"))
    )
    (net (code "163") (name "unconnected-(CN402-Pad163)") (class "Default")
      (node (ref "CN402") (pin "163") (pinfunction "163_163") (pintype "passive"))
    )
    (net (code "164") (name "unconnected-(CN402-Pad164)") (class "Default")
      (node (ref "CN402") (pin "164") (pinfunction "164_164") (pintype "passive"))
    )
    (net (code "165") (name "unconnected-(CN402-Pad165)") (class "Default")
      (node (ref "CN402") (pin "165") (pinfunction "165_165") (pintype "passive"))
    )
    (net (code "166") (name "unconnected-(CN402-Pad166)") (class "Default")
      (node (ref "CN402") (pin "166") (pinfunction "166_166") (pintype "passive"))
    )
    (net (code "167") (name "unconnected-(CN402-Pad167)") (class "Default")
      (node (ref "CN402") (pin "167") (pinfunction "167_167") (pintype "passive"))
    )
    (net (code "168") (name "unconnected-(CN402-Pad168)") (class "Default")
      (node (ref "CN402") (pin "168") (pinfunction "168_168") (pintype "passive"))
    )
    (net (code "169") (name "unconnected-(CN402-Pad169)") (class "Default")
      (node (ref "CN402") (pin "169") (pinfunction "169_169") (pintype "passive"))
    )
    (net (code "170") (name "unconnected-(CN402-Pad170)") (class "Default")
      (node (ref "CN402") (pin "170") (pinfunction "170_170") (pintype "passive"))
    )
    (net (code "171") (name "unconnected-(CN402-Pad171)") (class "Default")
      (node (ref "CN402") (pin "171") (pinfunction "171_171") (pintype "passive"))
    )
    (net (code "172") (name "unconnected-(CN402-Pad172)") (class "Default")
      (node (ref "CN402") (pin "172") (pinfunction "172_172") (pintype "passive"))
    )
    (net (code "173") (name "unconnected-(CN402-Pad173)") (class "Default")
      (node (ref "CN402") (pin "173") (pinfunction "173_173") (pintype "passive"))
    )
    (net (code "174") (name "unconnected-(CN402-Pad174)") (class "Default")
      (node (ref "CN402") (pin "174") (pinfunction "174_174") (pintype "passive"))
    )
    (net (code "175") (name "unconnected-(CN402-Pad175)") (class "Default")
      (node (ref "CN402") (pin "175") (pinfunction "175_175") (pintype "passive"))
    )
    (net (code "176") (name "unconnected-(CN402-Pad176)") (class "Default")
      (node (ref "CN402") (pin "176") (pinfunction "176_176") (pintype "passive"))
    )
    (net (code "177") (name "unconnected-(CN402-Pad177)") (class "Default")
      (node (ref "CN402") (pin "177") (pinfunction "177_177") (pintype "passive"))
    )
    (net (code "178") (name "unconnected-(CN402-Pad178)") (class "Default")
      (node (ref "CN402") (pin "178") (pinfunction "178_178") (pintype "passive"))
    )
    (net (code "179") (name "unconnected-(CN402-Pad179)") (class "Default")
      (node (ref "CN402") (pin "179") (pinfunction "179_179") (pintype "passive"))
    )
    (net (code "180") (name "unconnected-(CN402-Pad180)") (class "Default")
      (node (ref "CN402") (pin "180") (pinfunction "180_180") (pintype "passive"))
    )
    (net (code "181") (name "unconnected-(CN402-Pad181)") (class "Default")
      (node (ref "CN402") (pin "181") (pinfunction "181_181") (pintype "passive"))
    )
    (net (code "182") (name "unconnected-(CN402-Pad182)") (class "Default")
      (node (ref "CN402") (pin "182") (pinfunction "182_182") (pintype "passive"))
    )
    (net (code "183") (name "unconnected-(CN402-Pad183)") (class "Default")
      (node (ref "CN402") (pin "183") (pinfunction "183_183") (pintype "passive"))
    )
    (net (code "184") (name "unconnected-(CN402-Pad184)") (class "Default")
      (node (ref "CN402") (pin "184") (pinfunction "184_184") (pintype "passive"))
    )
    (net (code "185") (name "unconnected-(CN402-Pad185)") (class "Default")
      (node (ref "CN402") (pin "185") (pinfunction "185_185") (pintype "passive"))
    )
    (net (code "186") (name "unconnected-(CN402-Pad186)") (class "Default")
      (node (ref "CN402") (pin "186") (pinfunction "186_186") (pintype "passive"))
    )
    (net (code "187") (name "unconnected-(CN402-Pad187)") (class "Default")
      (node (ref "CN402") (pin "187") (pinfunction "187_187") (pintype "passive"))
    )
    (net (code "188") (name "unconnected-(CN402-Pad188)") (class "Default")
      (node (ref "CN402") (pin "188") (pinfunction "188_188") (pintype "passive"))
    )
    (net (code "189") (name "unconnected-(CN402-Pad189)") (class "Default")
      (node (ref "CN402") (pin "189") (pinfunction "189_189") (pintype "passive"))
    )
    (net (code "190") (name "unconnected-(CN402-Pad190)") (class "Default")
      (node (ref "CN402") (pin "190") (pinfunction "190_190") (pintype "passive"))
    )
    (net (code "191") (name "unconnected-(CN402-Pad191)") (class "Default")
      (node (ref "CN402") (pin "191") (pinfunction "191_191") (pintype "passive"))
    )
    (net (code "192") (name "unconnected-(CN402-Pad192)") (class "Default")
      (node (ref "CN402") (pin "192") (pinfunction "192_192") (pintype "passive"))
    )
    (net (code "193") (name "unconnected-(CN402-Pad193)") (class "Default")
      (node (ref "CN402") (pin "193") (pinfunction "193_193") (pintype "passive"))
    )
    (net (code "194") (name "unconnected-(CN402-Pad194)") (class "Default")
      (node (ref "CN402") (pin "194") (pinfunction "194_194") (pintype "passive"))
    )
    (net (code "195") (name "unconnected-(CN402-Pad195)") (class "Default")
      (node (ref "CN402") (pin "195") (pinfunction "195_195") (pintype "passive"))
    )
    (net (code "196") (name "unconnected-(CN402-Pad196)") (class "Default")
      (node (ref "CN402") (pin "196") (pinfunction "196_196") (pintype "passive"))
    )
    (net (code "197") (name "unconnected-(CN402-Pad197)") (class "Default")
      (node (ref "CN402") (pin "197") (pinfunction "197_197") (pintype "passive"))
    )
    (net (code "198") (name "unconnected-(CN402-Pad198)") (class "Default")
      (node (ref "CN402") (pin "198") (pinfunction "198_198") (pintype "passive"))
    )
    (net (code "199") (name "unconnected-(CN402-Pad199)") (class "Default")
      (node (ref "CN402") (pin "199") (pinfunction "199_199") (pintype "passive"))
    )
    (net (code "200") (name "unconnected-(CN402-Pad200)") (class "Default")
      (node (ref "CN402") (pin "200") (pinfunction "200_200") (pintype "passive"))
    )
    (net (code "201") (name "unconnected-(CN402-Pad201)") (class "Default")
      (node (ref "CN402") (pin "201") (pinfunction "201_201") (pintype "passive"))
    )
    (net (code "202") (name "unconnected-(CN402-Pad202)") (class "Default")
      (node (ref "CN402") (pin "202") (pinfunction "202_202") (pintype "passive"))
    )
    (net (code "203") (name "unconnected-(CN402-Pad203)") (class "Default")
      (node (ref "CN402") (pin "203") (pinfunction "203_203") (pintype "passive"))
    )
    (net (code "204") (name "unconnected-(CN402-Pad204)") (class "Default")
      (node (ref "CN402") (pin "204") (pinfunction "204_204") (pintype "passive"))
    )
    (net (code "205") (name "unconnected-(CN402-Pad205)") (class "Default")
      (node (ref "CN402") (pin "205") (pinfunction "205_205") (pintype "passive"))
    )
    (net (code "206") (name "unconnected-(CN402-Pad206)") (class "Default")
      (node (ref "CN402") (pin "206") (pinfunction "206_206") (pintype "passive"))
    )
    (net (code "207") (name "unconnected-(CN402-Pad207)") (class "Default")
      (node (ref "CN402") (pin "207") (pinfunction "207_207") (pintype "passive"))
    )
    (net (code "208") (name "unconnected-(CN402-Pad208)") (class "Default")
      (node (ref "CN402") (pin "208") (pinfunction "208_208") (pintype "passive"))
    )
    (net (code "209") (name "unconnected-(CN402-Pad209)") (class "Default")
      (node (ref "CN402") (pin "209") (pinfunction "209_209") (pintype "passive"))
    )
    (net (code "210") (name "unconnected-(CN402-Pad210)") (class "Default")
      (node (ref "CN402") (pin "210") (pinfunction "210_210") (pintype "passive"))
    )
    (net (code "211") (name "unconnected-(CN402-Pad211)") (class "Default")
      (node (ref "CN402") (pin "211") (pinfunction "211_211") (pintype "passive"))
    )
    (net (code "212") (name "unconnected-(CN402-Pad212)") (class "Default")
      (node (ref "CN402") (pin "212") (pinfunction "212_212") (pintype "passive"))
    )
    (net (code "213") (name "unconnected-(CN402-Pad213)") (class "Default")
      (node (ref "CN402") (pin "213") (pinfunction "213_213") (pintype "passive"))
    )
    (net (code "214") (name "unconnected-(CN402-Pad214)") (class "Default")
      (node (ref "CN402") (pin "214") (pinfunction "214_214") (pintype "passive"))
    )
    (net (code "215") (name "unconnected-(CN402-Pad215)") (class "Default")
      (node (ref "CN402") (pin "215") (pinfunction "215_215") (pintype "passive"))
    )
    (net (code "216") (name "unconnected-(CN402-Pad216)") (class "Default")
      (node (ref "CN402") (pin "216") (pinfunction "216_216") (pintype "passive"))
    )
    (net (code "217") (name "unconnected-(CN402-Pad217)") (class "Default")
      (node (ref "CN402") (pin "217") (pinfunction "217_217") (pintype "passive"))
    )
    (net (code "218") (name "unconnected-(CN402-Pad218)") (class "Default")
      (node (ref "CN402") (pin "218") (pinfunction "218_218") (pintype "passive"))
    )
    (net (code "219") (name "unconnected-(CN402-Pad219)") (class "Default")
      (node (ref "CN402") (pin "219") (pinfunction "219_219") (pintype "passive"))
    )
    (net (code "220") (name "unconnected-(CN402-Pad220)") (class "Default")
      (node (ref "CN402") (pin "220") (pinfunction "220_220") (pintype "passive"))
    )
    (net (code "221") (name "unconnected-(CN402-Pad221)") (class "Default")
      (node (ref "CN402") (pin "221") (pinfunction "221_221") (pintype "passive"))
    )
    (net (code "222") (name "unconnected-(CN402-Pad222)") (class "Default")
      (node (ref "CN402") (pin "222") (pinfunction "222_222") (pintype "passive"))
    )
    (net (code "223") (name "unconnected-(CN402-Pad223)") (class "Default")
      (node (ref "CN402") (pin "223") (pinfunction "223_223") (pintype "passive"))
    )
    (net (code "224") (name "unconnected-(CN402-Pad224)") (class "Default")
      (node (ref "CN402") (pin "224") (pinfunction "224_224") (pintype "passive"))
    )
    (net (code "225") (name "unconnected-(CN402-Pad225)") (class "Default")
      (node (ref "CN402") (pin "225") (pinfunction "225_225") (pintype "passive"))
    )
    (net (code "226") (name "unconnected-(CN402-Pad226)") (class "Default")
      (node (ref "CN402") (pin "226") (pinfunction "226_226") (pintype "passive"))
    )
    (net (code "227") (name "unconnected-(CN402-Pad227)") (class "Default")
      (node (ref "CN402") (pin "227") (pinfunction "227_227") (pintype "passive"))
    )
    (net (code "228") (name "unconnected-(CN402-Pad228)") (class "Default")
      (node (ref "CN402") (pin "228") (pinfunction "228_228") (pintype "passive"))
    )
    (net (code "229") (name "unconnected-(CN402-Pad229)") (class "Default")
      (node (ref "CN402") (pin "229") (pinfunction "229_229") (pintype "passive"))
    )
    (net (code "230") (name "unconnected-(CN402-Pad230)") (class "Default")
      (node (ref "CN402") (pin "230") (pinfunction "230_230") (pintype "passive"))
    )
    (net (code "231") (name "unconnected-(CN402-Pad231)") (class "Default")
      (node (ref "CN402") (pin "231") (pinfunction "231_231") (pintype "passive"))
    )
    (net (code "232") (name "unconnected-(CN402-Pad232)") (class "Default")
      (node (ref "CN402") (pin "232") (pinfunction "232_232") (pintype "passive"))
    )
    (net (code "233") (name "unconnected-(CN402-Pad233)") (class "Default")
      (node (ref "CN402") (pin "233") (pinfunction "233_233") (pintype "passive"))
    )
    (net (code "234") (name "unconnected-(CN402-Pad234)") (class "Default")
      (node (ref "CN402") (pin "234") (pinfunction "234_234") (pintype "passive"))
    )
    (net (code "235") (name "unconnected-(CN402-Pad235)") (class "Default")
      (node (ref "CN402") (pin "235") (pinfunction "235_235") (pintype "passive"))
    )
    (net (code "236") (name "unconnected-(CN402-Pad236)") (class "Default")
      (node (ref "CN402") (pin "236") (pinfunction "236_236") (pintype "passive"))
    )
    (net (code "237") (name "unconnected-(CN402-Pad237)") (class "Default")
      (node (ref "CN402") (pin "237") (pinfunction "237_237") (pintype "passive"))
    )
    (net (code "238") (name "unconnected-(CN402-Pad238)") (class "Default")
      (node (ref "CN402") (pin "238") (pinfunction "238_238") (pintype "passive"))
    )
    (net (code "239") (name "unconnected-(CN402-Pad239)") (class "Default")
      (node (ref "CN402") (pin "239") (pinfunction "239_239") (pintype "passive"))
    )
    (net (code "240") (name "unconnected-(CN402-Pad240)") (class "Default")
      (node (ref "CN402") (pin "240") (pinfunction "240_240") (pintype "passive"))
    )
    (net (code "241") (name "unconnected-(CN402-Pad241)") (class "Default")
      (node (ref "CN402") (pin "241") (pinfunction "241_241") (pintype "passive"))
    )
    (net (code "242") (name "unconnected-(CN402-Pad242)") (class "Default")
      (node (ref "CN402") (pin "242") (pinfunction "242_242") (pintype "passive"))
    )
    (net (code "243") (name "unconnected-(CN402-Pad243)") (class "Default")
      (node (ref "CN402") (pin "243") (pinfunction "243_243") (pintype "passive"))
    )
    (net (code "244") (name "unconnected-(CN402-Pad244)") (class "Default")
      (node (ref "CN402") (pin "244") (pinfunction "244_244") (pintype "passive"))
    )
    (net (code "245") (name "unconnected-(CN402-Pad245)") (class "Default")
      (node (ref "CN402") (pin "245") (pinfunction "245_245") (pintype "passive"))
    )
    (net (code "246") (name "unconnected-(CN402-Pad246)") (class "Default")
      (node (ref "CN402") (pin "246") (pinfunction "246_246") (pintype "passive"))
    )
    (net (code "247") (name "unconnected-(CN402-Pad247)") (class "Default")
      (node (ref "CN402") (pin "247") (pinfunction "247_247") (pintype "passive"))
    )
    (net (code "248") (name "unconnected-(CN402-Pad248)") (class "Default")
      (node (ref "CN402") (pin "248") (pinfunction "248_248") (pintype "passive"))
    )
    (net (code "249") (name "unconnected-(CN402-Pad249)") (class "Default")
      (node (ref "CN402") (pin "249") (pinfunction "249_249") (pintype "passive"))
    )
    (net (code "250") (name "unconnected-(CN402-Pad250)") (class "Default")
      (node (ref "CN402") (pin "250") (pinfunction "250_250") (pintype "passive"))
    )
    (net (code "251") (name "unconnected-(CN402-Pad251)") (class "Default")
      (node (ref "CN402") (pin "251") (pinfunction "251_251") (pintype "passive"))
    )
    (net (code "252") (name "unconnected-(CN402-Pad252)") (class "Default")
      (node (ref "CN402") (pin "252") (pinfunction "252_252") (pintype "passive"))
    )
    (net (code "253") (name "unconnected-(CN402-Pad253)") (class "Default")
      (node (ref "CN402") (pin "253") (pinfunction "253_253") (pintype "passive"))
    )
    (net (code "254") (name "unconnected-(CN402-Pad254)") (class "Default")
      (node (ref "CN402") (pin "254") (pinfunction "254_254") (pintype "passive"))
    )
    (net (code "255") (name "unconnected-(CN402-Pad255)") (class "Default")
      (node (ref "CN402") (pin "255") (pinfunction "255_255") (pintype "passive"))
    )
    (net (code "256") (name "unconnected-(CN402-Pad256)") (class "Default")
      (node (ref "CN402") (pin "256") (pinfunction "256_256") (pintype "passive"))
    )
    (net (code "257") (name "unconnected-(CN402-Pad257)") (class "Default")
      (node (ref "CN402") (pin "257") (pinfunction "257_257") (pintype "passive"))
    )
    (net (code "258") (name "unconnected-(CN402-Pad258)") (class "Default")
      (node (ref "CN402") (pin "258") (pinfunction "258_258") (pintype "passive"))
    )
    (net (code "259") (name "unconnected-(CN402-Pad259)") (class "Default")
      (node (ref "CN402") (pin "259") (pinfunction "259_259") (pintype "passive"))
    )
    (net (code "260") (name "unconnected-(CN402-Pad260)") (class "Default")
      (node (ref "CN402") (pin "260") (pinfunction "260_260") (pintype "passive"))
    )
    (net (code "261") (name "unconnected-(CN402-PadMP)") (class "Default")
      (node (ref "CN402") (pin "MP") (pinfunction "MP_MP") (pintype "passive+no_connect"))
    )
  )
)
